# PWR_REVX.net
KiCad netlist of a schematic drawn in Altium Designer
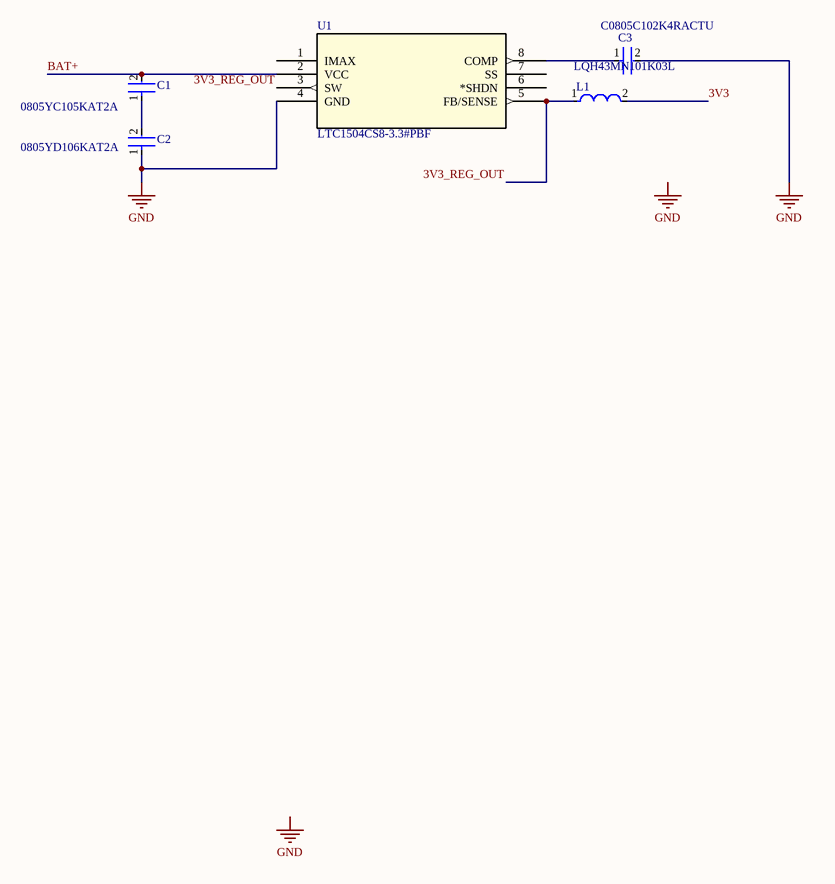
[diagram p0: PWR_REVX.SchDoc]

(export (version "E")
  (design (tool "Eeschema 10.0.6"))
  (components
    (comp (ref "C1")
      (value "0805YC105KAT2A")
      (footprint "FP-0805-L_2_01_0_2-W_1_25-IPC_A")
      (description "General Purpose Ceramic Capacitor, 0805, 1uF, 10%, X7R, 15%, 16V")
      (fields (field (name "TOLERANCE") "10%") (field (name "VOLTAGE") "16V"))
      (libsource (lib "Altium Content Vault") (part "b4654b650e69147ec39a6b967a45e02"))
    )
    (comp (ref "C2")
      (value "0805YD106KAT2A")
      (footprint "FP-0805-L_2_01_0_2-W_1_25-IPC_A")
      (description "General Purpose Ceramic Capacitor, 0805, 10uF, 10%, X5R, 15%, 16V")
      (fields (field (name "VOLTAGE") "16V") (field (name "TOLERANCE") "10%"))
      (libsource (lib "Altium Content Vault") (part "02cd4be3c70576c341d710602a673aa"))
    )
    (comp (ref "C3")
      (value "C0805C102K4RACTU")
      (footprint "FP-C0805C-DN-MFG")
      (description "C0805 1,000 pF X7R 30ppm/°C 10.00% 16 V")
      (fields (field (name "OCTOPART") "https://octopart.com/c0805c102k4ractu-kemet-8375752"))
      (libsource (lib "Altium Content Vault") (part "b4654b650e69147ec39a6b967a45e02"))
    )
    (comp (ref "L1")
      (value "LQH43MN101K03L")
      (footprint "FP-LQH43CN_03-MFG")
      (description "Wire Wound Ferrite Inductor for General Circuits 100μH ±10% 2.5Ω 160mA 1812")
      (fields (field (name "TOLERANCE") "10%"))
      (libsource (lib "Altium Content Vault") (part "725321dda6339637d4d059423bc1c3c"))
    )
    (comp (ref "U1")
      (value "LTC1504CS8-3.3#PBF")
      (footprint "LT1303CS8-5&hash_PBF:SO-8_S_LIT")
      (description "No Description Available")
      (fields (field (name "COPYRIGHT") "Copyright (C) 2022 Ultra Librarian. All rights reserved."))
      (libsource (lib "POWER_REVX") (part "LTC1504CS8-3.3#PBF"))
    )
  )
  (nets
    (net (code "1") (name "/3V3") (class "Default")
      (node (ref "L1") (pin "2") (pinfunction "2_2") (pintype "passive"))
    )
    (net (code "2") (name "/3V3_REG_OUT") (class "Default")
      (node (ref "L1") (pin "1") (pinfunction "1_1") (pintype "passive"))
      (node (ref "U1") (pin "3") (pinfunction "SW_3") (pintype "output"))
      (node (ref "U1") (pin "5") (pinfunction "FB/SENSE_5") (pintype "output"))
    )
    (net (code "3") (name "/BAT+") (class "Default")
      (node (ref "C1") (pin "2") (pinfunction "2_2") (pintype "passive"))
      (node (ref "U1") (pin "2") (pinfunction "VCC_2") (pintype "power_in"))
    )
    (net (code "4") (name "GND") (class "Default")
      (node (ref "C2") (pin "1") (pinfunction "1_1") (pintype "passive"))
      (node (ref "C3") (pin "2") (pinfunction "2_2") (pintype "passive"))
      (node (ref "U1") (pin "4") (pinfunction "GND_4") (pintype "power_in"))
    )
    (net (code "5") (name "Net-(C1-Pad1)") (class "Default")
      (node (ref "C1") (pin "1") (pinfunction "1_1") (pintype "passive"))
      (node (ref "C2") (pin "2") (pinfunction "2_2") (pintype "passive"))
    )
    (net (code "6") (name "Net-(U1-COMP)") (class "Default")
      (node (ref "C3") (pin "1") (pinfunction "1_1") (pintype "passive"))
      (node (ref "U1") (pin "8") (pinfunction "COMP_8") (pintype "output"))
    )
    (net (code "7") (name "unconnected-(U1-*SHDN-Pad6)") (class "Default")
      (node (ref "U1") (pin "6") (pinfunction "*SHDN_6") (pintype "passive"))
    )
    (net (code "8") (name "unconnected-(U1-IMAX-Pad1)") (class "Default")
      (node (ref "U1") (pin "1") (pinfunction "IMAX_1") (pintype "passive"))
    )
    (net (code "9") (name "unconnected-(U1-SS-Pad7)") (class "Default")
      (node (ref "U1") (pin "7") (pinfunction "SS_7") (pintype "passive"))
    )
  )
)
